# TPS75501_1V8.net
KiCad netlist of a schematic drawn in Altium Designer
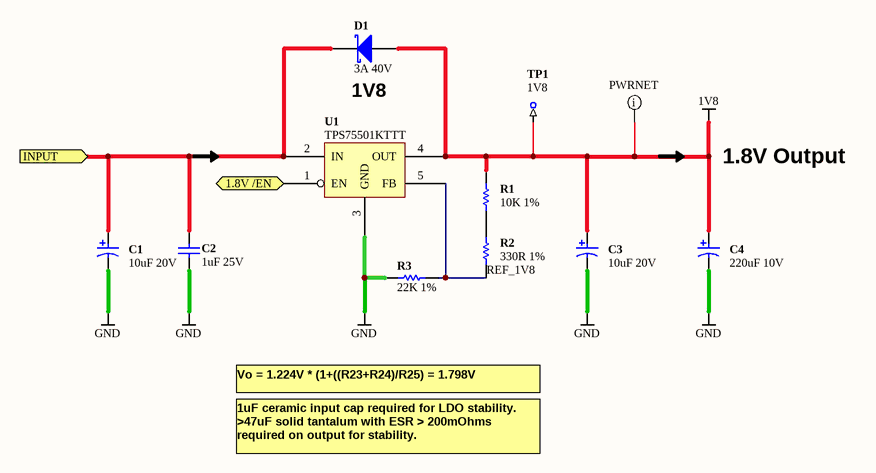
[diagram p0: TPS75501_1V8.SchDoc]

(export (version "E")
  (design (tool "Eeschema 10.0.6"))
  (components
    (comp (ref "C1")
      (value "10uF 20V")
      (footprint "CAPC3528-STAR")
      (description "Capacitor, Tantalum, 10uF 10% 20V MCCT-B (3528)")
      (fields (field (name "TOLERANCE") "10 %"))
      (libsource (lib "altium-import") (part "root_0_CAP-P_"))
    )
    (comp (ref "C2")
      (value "1uF 25V")
      (footprint "CAPC3216-STAR")
      (description "Capacitor, Ceramic, 1uF 10% 25V 1206 (3216) X7R")
      (fields (field (name "TOLERANCE") "10 %"))
      (libsource (lib "altium-import") (part "root_0_CAP-NP_"))
    )
    (comp (ref "C3")
      (value "10uF 20V")
      (footprint "CAPC3528-STAR")
      (description "Capacitor, Tantalum, 10uF 10% 20V MCCT-B (3528)")
      (fields (field (name "TOLERANCE") "10 %"))
      (libsource (lib "altium-import") (part "root_0_CAP-P_"))
    )
    (comp (ref "C4")
      (value "220uF 10V")
      (footprint "CAPC7343-STAR")
      (description "Capacitor, Tantalum, 220uF 10% 10V MCCT-D (7343-31)")
      (fields (field (name "TOLERANCE") "10 %"))
      (libsource (lib "altium-import") (part "root_0_CAP-P_"))
    )
    (comp (ref "D1")
      (value "3A 40V")
      (footprint "DIOM5027")
      (description "Schottky Diode, 3A 40V")
      (libsource (lib "altium-import") (part "root_2_DIO-SCHOTTKY-1S_"))
    )
    (comp (ref "R1")
      (value "10K 1%")
      (footprint "RESC1005-STAR")
      (description "Resistor, 10K 1% 0402 (1005)")
      (fields (field (name "TOLERANCE") "1 %"))
      (libsource (lib "altium-import") (part "root_0_RES_"))
    )
    (comp (ref "R2")
      (value "330R 1%")
      (footprint "RESC1005-STAR")
      (description "Resistor, 330R 1% 0402 (1005)")
      (fields (field (name "TOLERANCE") "1 %"))
      (libsource (lib "altium-import") (part "root_0_RES_"))
    )
    (comp (ref "R3")
      (value "22K 1%")
      (footprint "RESC1005-STAR")
      (description "Resistor, 22K 1% 0402 (1005)")
      (fields (field (name "TOLERANCE") "1 %"))
      (libsource (lib "altium-import") (part "root_1_RES_"))
    )
    (comp (ref "TP1")
      (value "1V8")
      (footprint "TestPin")
      (description "Test Point, PCB Mount with Silkscreen Box")
      (libsource (lib "AltiumDesignLibrary") (part "TestPin"))
    )
    (comp (ref "U1")
      (value "TPS75501KTTT")
      (footprint "TO-263")
      (description "TPS75501KTTT, 5A, Low Dropout, Adjustable, Linear Voltage Regulator, TO-263")
      (libsource (lib "altium-import") (part "root_0_TPS75501_"))
    )
  )
  (nets
    (net (code "1") (name "/1.8V {slash}EN") (class "Default")
      (node (ref "U1") (pin "1") (pinfunction "EN_1") (pintype "passive"))
    )
    (net (code "2") (name "/INPUT") (class "Default")
      (node (ref "C1") (pin "1") (pinfunction "1_1") (pintype "passive"))
      (node (ref "C2") (pin "1") (pinfunction "1_1") (pintype "passive"))
      (node (ref "D1") (pin "2") (pinfunction "K_2") (pintype "passive"))
      (node (ref "U1") (pin "2") (pinfunction "IN_2") (pintype "passive"))
    )
    (net (code "3") (name "/REF_1V8") (class "Default")
      (node (ref "R2") (pin "2") (pinfunction "2_2") (pintype "passive"))
      (node (ref "R3") (pin "2") (pinfunction "2_2") (pintype "passive"))
      (node (ref "U1") (pin "5") (pinfunction "FB_5") (pintype "passive"))
    )
    (net (code "4") (name "1V8") (class "Default")
      (node (ref "C3") (pin "1") (pinfunction "1_1") (pintype "passive"))
      (node (ref "C4") (pin "1") (pinfunction "1_1") (pintype "passive"))
      (node (ref "D1") (pin "1") (pinfunction "A_1") (pintype "passive"))
      (node (ref "R1") (pin "1") (pinfunction "1_1") (pintype "passive"))
      (node (ref "TP1") (pin "1") (pinfunction "1_1") (pintype "input"))
      (node (ref "U1") (pin "4") (pinfunction "OUT_4") (pintype "passive"))
    )
    (net (code "5") (name "GND") (class "Default")
      (node (ref "C1") (pin "2") (pinfunction "2_2") (pintype "passive"))
      (node (ref "C2") (pin "2") (pinfunction "2_2") (pintype "passive"))
      (node (ref "C3") (pin "2") (pinfunction "2_2") (pintype "passive"))
      (node (ref "C4") (pin "2") (pinfunction "2_2") (pintype "passive"))
      (node (ref "R3") (pin "1") (pinfunction "1_1") (pintype "passive"))
      (node (ref "U1") (pin "3") (pinfunction "GND_3") (pintype "passive"))
    )
    (net (code "6") (name "Net-(R1-Pad2)") (class "Default")
      (node (ref "R1") (pin "2") (pinfunction "2_2") (pintype "passive"))
      (node (ref "R2") (pin "1") (pinfunction "1_1") (pintype "passive"))
    )
  )
)
